# STM32_CAN-USB.net
KiCad netlist of a schematic drawn in EAGLE
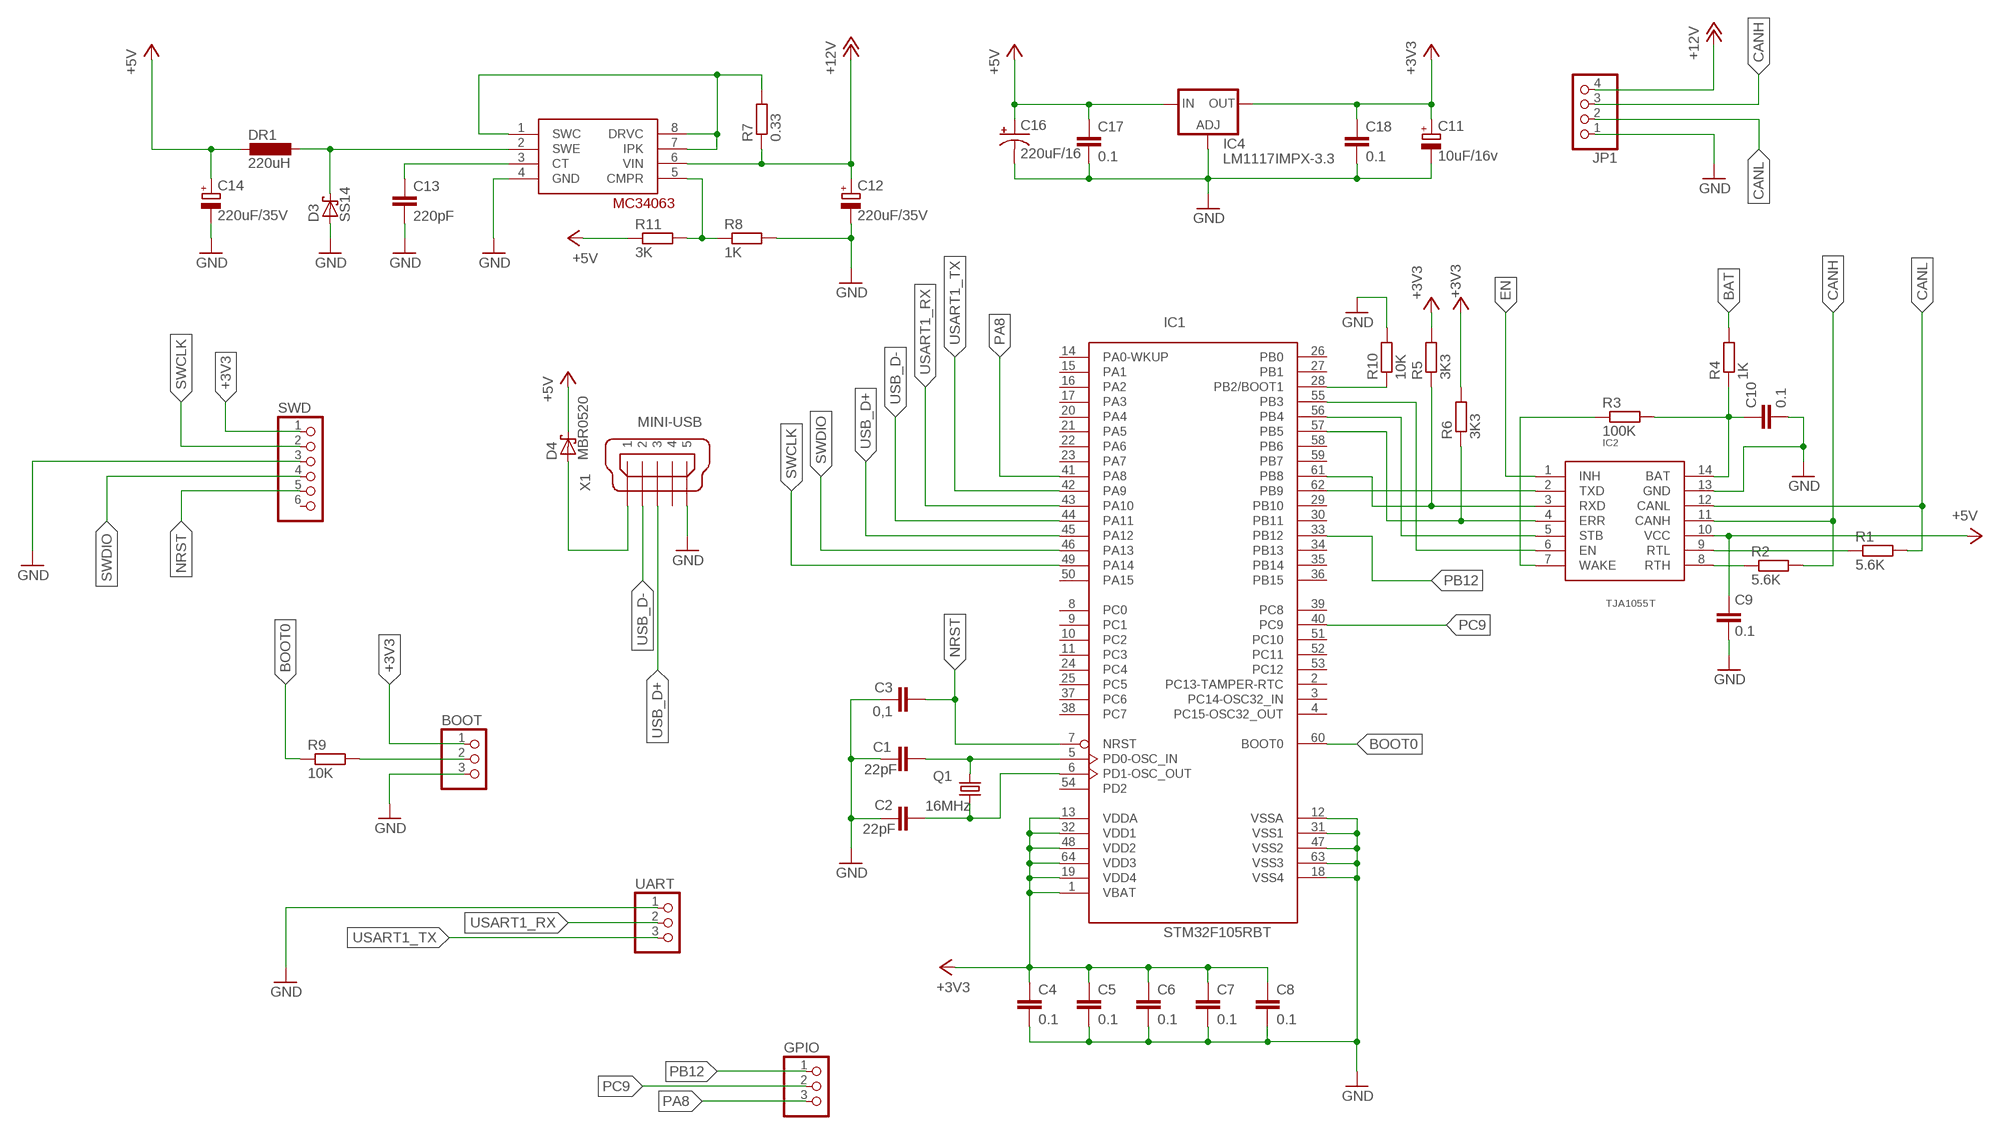
[diagram p0: schematic, sheet 1]

(export (version "E")
  (design (tool "Eeschema 10.0.6"))
  (components
    (comp (ref "BOOT")
      (value "PINHD-1X3")
      (footprint "eagle-import:1X03")
      (libsource (lib "eagle-import") (part "PINHD-1X3"))
    )
    (comp (ref "C1")
      (value "22pF")
      (footprint "eagle-import:C0805")
      (libsource (lib "eagle-import") (part "C-EUC0805"))
    )
    (comp (ref "C2")
      (value "22pF")
      (footprint "eagle-import:C0805")
      (libsource (lib "eagle-import") (part "C-EUC0805"))
    )
    (comp (ref "C3")
      (value "0,1")
      (footprint "eagle-import:C0805")
      (libsource (lib "eagle-import") (part "C-EUC0805"))
    )
    (comp (ref "C4")
      (value "0.1")
      (footprint "eagle-import:C0805")
      (libsource (lib "eagle-import") (part "C-EUC0805"))
    )
    (comp (ref "C5")
      (value "0.1")
      (footprint "eagle-import:C0805")
      (libsource (lib "eagle-import") (part "C-EUC0805"))
    )
    (comp (ref "C6")
      (value "0.1")
      (footprint "eagle-import:C0805")
      (libsource (lib "eagle-import") (part "C-EUC0805"))
    )
    (comp (ref "C7")
      (value "0.1")
      (footprint "eagle-import:C0805")
      (libsource (lib "eagle-import") (part "C-EUC0805"))
    )
    (comp (ref "C8")
      (value "0.1")
      (footprint "eagle-import:C0805")
      (libsource (lib "eagle-import") (part "C-EUC0805"))
    )
    (comp (ref "C9")
      (value "0.1")
      (footprint "eagle-import:C0805")
      (libsource (lib "eagle-import") (part "C-EUC0805"))
    )
    (comp (ref "C10")
      (value "0.1")
      (footprint "eagle-import:C0805")
      (libsource (lib "eagle-import") (part "C-EUC0805"))
    )
    (comp (ref "C11")
      (value "10uF/16v")
      (footprint "eagle-import:SMC_A")
      (libsource (lib "eagle-import") (part "CPOL-EUSMCA"))
    )
    (comp (ref "C12")
      (value "220uF/35V")
      (footprint "eagle-import:153CLV-0810")
      (libsource (lib "eagle-import") (part "CPOL-EU153CLV-0810"))
    )
    (comp (ref "C13")
      (value "220pF")
      (footprint "eagle-import:C0805")
      (libsource (lib "eagle-import") (part "C-EUC0805"))
    )
    (comp (ref "C14")
      (value "220uF/35V")
      (footprint "eagle-import:153CLV-0810")
      (libsource (lib "eagle-import") (part "CPOL-EU153CLV-0810"))
    )
    (comp (ref "C16")
      (value "220uF/16")
      (footprint "eagle-import:153CLV-0605")
      (libsource (lib "eagle-import") (part "CPOL-US153CLV-0605"))
    )
    (comp (ref "C17")
      (value "0.1")
      (footprint "eagle-import:C0805")
      (libsource (lib "eagle-import") (part "C-EUC0805"))
    )
    (comp (ref "C18")
      (value "0.1")
      (footprint "eagle-import:C0805")
      (libsource (lib "eagle-import") (part "C-EUC0805"))
    )
    (comp (ref "D3")
      (value "SS14")
      (footprint "eagle-import:SMA")
      (libsource (lib "eagle-import") (part "SS14"))
    )
    (comp (ref "D4")
      (value "MBR0520")
      (footprint "eagle-import:SOD123")
      (libsource (lib "eagle-import") (part "MBR0520"))
    )
    (comp (ref "DR1")
      (value "220uH")
      (footprint "eagle-import:MS85")
      (libsource (lib "eagle-import") (part "CDRH127"))
    )
    (comp (ref "GPIO")
      (value "PINHD-1X3")
      (footprint "eagle-import:1X03")
      (libsource (lib "eagle-import") (part "PINHD-1X3"))
    )
    (comp (ref "IC1")
      (value "STM32F105RBT")
      (footprint "eagle-import:LQFP64")
      (libsource (lib "eagle-import") (part "STM32F105RTB"))
    )
    (comp (ref "IC2")
      (value "TJA1055T")
      (footprint "eagle-import:SO-14W")
      (libsource (lib "eagle-import") (part "TJA1054T"))
    )
    (comp (ref "IC4")
      (value "LM1117IMPX-3.3")
      (footprint "eagle-import:SOT223")
      (libsource (lib "eagle-import") (part "LM1117IMPX-3.3"))
    )
    (comp (ref "JP1")
      (value "PINHD-1X4")
      (footprint "eagle-import:1X04")
      (libsource (lib "eagle-import") (part "PINHD-1X4"))
    )
    (comp (ref "MC34063")
      (value "MC34063")
      (footprint "eagle-import:SO8")
      (libsource (lib "eagle-import") (part "MC34063"))
    )
    (comp (ref "Q1")
      (value "16MHz")
      (footprint "eagle-import:HC49UP")
      (libsource (lib "eagle-import") (part "CRYSTALHC49UP"))
    )
    (comp (ref "R1")
      (value "5.6K")
      (footprint "eagle-import:R0805")
      (libsource (lib "eagle-import") (part "R-EU_R0805"))
    )
    (comp (ref "R2")
      (value "5.6K")
      (footprint "eagle-import:R0805")
      (libsource (lib "eagle-import") (part "R-EU_R0805"))
    )
    (comp (ref "R3")
      (value "100K")
      (footprint "eagle-import:R0805")
      (libsource (lib "eagle-import") (part "R-EU_R0805"))
    )
    (comp (ref "R4")
      (value "1K")
      (footprint "eagle-import:R0805")
      (libsource (lib "eagle-import") (part "R-EU_R0805"))
    )
    (comp (ref "R5")
      (value "3K3")
      (footprint "eagle-import:R0805")
      (libsource (lib "eagle-import") (part "R-EU_R0805"))
    )
    (comp (ref "R6")
      (value "3K3")
      (footprint "eagle-import:R0805")
      (libsource (lib "eagle-import") (part "R-EU_R0805"))
    )
    (comp (ref "R7")
      (value "0.33")
      (footprint "eagle-import:R0805")
      (libsource (lib "eagle-import") (part "R-EU_R0805"))
    )
    (comp (ref "R8")
      (value "1K")
      (footprint "eagle-import:R0805")
      (libsource (lib "eagle-import") (part "R-EU_R0805"))
    )
    (comp (ref "R9")
      (value "10K")
      (footprint "eagle-import:R0805")
      (libsource (lib "eagle-import") (part "R-EU_R0805"))
    )
    (comp (ref "R10")
      (value "10K")
      (footprint "eagle-import:R0805")
      (libsource (lib "eagle-import") (part "R-EU_R0805"))
    )
    (comp (ref "R11")
      (value "3K")
      (footprint "eagle-import:R0805")
      (libsource (lib "eagle-import") (part "R-EU_R0805"))
    )
    (comp (ref "SWD")
      (value "PINHD-1X6")
      (footprint "eagle-import:1X06")
      (libsource (lib "eagle-import") (part "PINHD-1X6"))
    )
    (comp (ref "UART")
      (value "PINHD-1X3")
      (footprint "eagle-import:1X03")
      (libsource (lib "eagle-import") (part "PINHD-1X3"))
    )
    (comp (ref "X1")
      (value "MINI-USB")
      (footprint "eagle-import:UX60-MB-5ST")
      (libsource (lib "eagle-import") (part "MINI-USB-UX60-MB-5ST"))
    )
  )
  (nets
    (net (code "1") (name "+3V3") (class "Default")
      (node (ref "BOOT") (pin "1") (pinfunction "1_1") (pintype "passive"))
      (node (ref "C11") (pin "+") (pinfunction "+_+") (pintype "passive"))
      (node (ref "C18") (pin "1") (pinfunction "1_1") (pintype "passive"))
      (node (ref "C4") (pin "1") (pinfunction "1_1") (pintype "passive"))
      (node (ref "C5") (pin "1") (pinfunction "1_1") (pintype "passive"))
      (node (ref "C6") (pin "1") (pinfunction "1_1") (pintype "passive"))
      (node (ref "C7") (pin "1") (pinfunction "1_1") (pintype "passive"))
      (node (ref "C8") (pin "1") (pinfunction "1_1") (pintype "passive"))
      (node (ref "IC1") (pin "1") (pinfunction "VBAT_1") (pintype "power_in"))
      (node (ref "IC1") (pin "13") (pinfunction "VDDA_13") (pintype "power_in"))
      (node (ref "IC1") (pin "19") (pinfunction "VDD4_19") (pintype "power_in"))
      (node (ref "IC1") (pin "32") (pinfunction "VDD1_32") (pintype "power_in"))
      (node (ref "IC1") (pin "48") (pinfunction "VDD2_48") (pintype "power_in"))
      (node (ref "IC1") (pin "64") (pinfunction "VDD3_64") (pintype "power_in"))
      (node (ref "IC4") (pin "2") (pinfunction "OUT_2") (pintype "passive"))
      (node (ref "IC4") (pin "4") (pinfunction "OUT_4") (pintype "passive"))
      (node (ref "R5") (pin "2") (pinfunction "2_2") (pintype "passive"))
      (node (ref "R6") (pin "2") (pinfunction "2_2") (pintype "passive"))
      (node (ref "SWD") (pin "1") (pinfunction "1_1") (pintype "passive"))
    )
    (net (code "2") (name "+5V") (class "Default")
      (node (ref "C14") (pin "+") (pinfunction "+_+") (pintype "passive"))
      (node (ref "C16") (pin "+") (pinfunction "+_+") (pintype "passive"))
      (node (ref "C17") (pin "1") (pinfunction "1_1") (pintype "passive"))
      (node (ref "C9") (pin "1") (pinfunction "1_1") (pintype "passive"))
      (node (ref "D4") (pin "C") (pinfunction "C_C") (pintype "passive"))
      (node (ref "DR1") (pin "P$1") (pinfunction "1_P$1") (pintype "passive"))
      (node (ref "IC2") (pin "10") (pinfunction "VCC_10") (pintype "power_in"))
      (node (ref "IC4") (pin "3") (pinfunction "IN_3") (pintype "input"))
      (node (ref "R11") (pin "1") (pinfunction "1_1") (pintype "passive"))
    )
    (net (code "3") (name "+12V") (class "Default")
      (node (ref "C12") (pin "+") (pinfunction "+_+") (pintype "passive"))
      (node (ref "JP1") (pin "4") (pinfunction "4_4") (pintype "passive"))
      (node (ref "MC34063") (pin "6") (pinfunction "VIN_6") (pintype "power_in"))
      (node (ref "R7") (pin "1") (pinfunction "1_1") (pintype "passive"))
    )
    (net (code "4") (name "BAT") (class "Default")
      (node (ref "R4") (pin "2") (pinfunction "2_2") (pintype "passive"))
    )
    (net (code "5") (name "BOOT0") (class "Default")
      (node (ref "IC1") (pin "60") (pinfunction "BOOT0_60") (pintype "input"))
      (node (ref "R9") (pin "1") (pinfunction "1_1") (pintype "passive"))
    )
    (net (code "6") (name "CANH") (class "Default")
      (node (ref "IC2") (pin "11") (pinfunction "CANH_11") (pintype "bidirectional"))
      (node (ref "JP1") (pin "3") (pinfunction "3_3") (pintype "passive"))
      (node (ref "R2") (pin "2") (pinfunction "2_2") (pintype "passive"))
    )
    (net (code "7") (name "CANL") (class "Default")
      (node (ref "IC2") (pin "12") (pinfunction "CANL_12") (pintype "bidirectional"))
      (node (ref "JP1") (pin "2") (pinfunction "2_2") (pintype "passive"))
      (node (ref "R1") (pin "2") (pinfunction "2_2") (pintype "passive"))
    )
    (net (code "8") (name "EN") (class "Default")
      (node (ref "IC2") (pin "1") (pinfunction "INH_1") (pintype "output"))
    )
    (net (code "9") (name "GND") (class "Default")
      (node (ref "BOOT") (pin "3") (pinfunction "3_3") (pintype "passive"))
      (node (ref "C1") (pin "2") (pinfunction "2_2") (pintype "passive"))
      (node (ref "C10") (pin "2") (pinfunction "2_2") (pintype "passive"))
      (node (ref "C11") (pin "-") (pinfunction "-_-") (pintype "passive"))
      (node (ref "C12") (pin "-") (pinfunction "-_-") (pintype "passive"))
      (node (ref "C13") (pin "2") (pinfunction "2_2") (pintype "passive"))
      (node (ref "C14") (pin "-") (pinfunction "-_-") (pintype "passive"))
      (node (ref "C16") (pin "-") (pinfunction "-_-") (pintype "passive"))
      (node (ref "C17") (pin "2") (pinfunction "2_2") (pintype "passive"))
      (node (ref "C18") (pin "2") (pinfunction "2_2") (pintype "passive"))
      (node (ref "C2") (pin "2") (pinfunction "2_2") (pintype "passive"))
      (node (ref "C3") (pin "1") (pinfunction "1_1") (pintype "passive"))
      (node (ref "C4") (pin "2") (pinfunction "2_2") (pintype "passive"))
      (node (ref "C5") (pin "2") (pinfunction "2_2") (pintype "passive"))
      (node (ref "C6") (pin "2") (pinfunction "2_2") (pintype "passive"))
      (node (ref "C7") (pin "2") (pinfunction "2_2") (pintype "passive"))
      (node (ref "C8") (pin "2") (pinfunction "2_2") (pintype "passive"))
      (node (ref "C9") (pin "2") (pinfunction "2_2") (pintype "passive"))
      (node (ref "D3") (pin "A") (pinfunction "A_A") (pintype "passive"))
      (node (ref "IC1") (pin "12") (pinfunction "VSSA_12") (pintype "power_in"))
      (node (ref "IC1") (pin "18") (pinfunction "VSS4_18") (pintype "power_in"))
      (node (ref "IC1") (pin "31") (pinfunction "VSS1_31") (pintype "power_in"))
      (node (ref "IC1") (pin "47") (pinfunction "VSS2_47") (pintype "power_in"))
      (node (ref "IC1") (pin "63") (pinfunction "VSS3_63") (pintype "power_in"))
      (node (ref "IC2") (pin "13") (pinfunction "GND_13") (pintype "power_in"))
      (node (ref "IC4") (pin "1") (pinfunction "ADJ_1") (pintype "input"))
      (node (ref "JP1") (pin "1") (pinfunction "1_1") (pintype "passive"))
      (node (ref "MC34063") (pin "4") (pinfunction "GND_4") (pintype "power_in"))
      (node (ref "R10") (pin "2") (pinfunction "2_2") (pintype "passive"))
      (node (ref "R8") (pin "2") (pinfunction "2_2") (pintype "passive"))
      (node (ref "SWD") (pin "3") (pinfunction "3_3") (pintype "passive"))
      (node (ref "UART") (pin "1") (pinfunction "1_1") (pintype "passive"))
      (node (ref "X1") (pin "5") (pinfunction "5_5") (pintype "input"))
      (node (ref "X1") (pin "M1") (pinfunction "5_M1") (pintype "input"))
      (node (ref "X1") (pin "M2") (pinfunction "5_M2") (pintype "input"))
    )
    (net (code "10") (name "NRST") (class "Default")
      (node (ref "C3") (pin "2") (pinfunction "2_2") (pintype "passive"))
      (node (ref "IC1") (pin "7") (pinfunction "NRST_7") (pintype "bidirectional"))
      (node (ref "SWD") (pin "5") (pinfunction "5_5") (pintype "passive"))
    )
    (net (code "11") (name "Net-(BOOT-Pad2)") (class "Default")
      (node (ref "BOOT") (pin "2") (pinfunction "2_2") (pintype "passive"))
      (node (ref "R9") (pin "2") (pinfunction "2_2") (pintype "passive"))
    )
    (net (code "12") (name "Net-(D4-PadA)") (class "Default")
      (node (ref "D4") (pin "A") (pinfunction "A_A") (pintype "passive"))
      (node (ref "X1") (pin "1") (pinfunction "1_1") (pintype "input"))
    )
    (net (code "13") (name "Net-(DR1-2)") (class "Default")
      (node (ref "D3") (pin "C") (pinfunction "C_C") (pintype "passive"))
      (node (ref "DR1") (pin "P$2") (pinfunction "2_P$2") (pintype "passive"))
      (node (ref "MC34063") (pin "2") (pinfunction "SWE_2") (pintype "output"))
    )
    (net (code "14") (name "Net-(IC1-PB2{slash}BOOT1)") (class "Default")
      (node (ref "IC1") (pin "28") (pinfunction "PB2/BOOT1_28") (pintype "bidirectional"))
      (node (ref "R10") (pin "1") (pinfunction "1_1") (pintype "passive"))
    )
    (net (code "15") (name "Net-(IC1-PB3)") (class "Default")
      (node (ref "IC1") (pin "55") (pinfunction "PB3_55") (pintype "bidirectional"))
      (node (ref "IC2") (pin "6") (pinfunction "EN_6") (pintype "input"))
    )
    (net (code "16") (name "Net-(IC1-PB4)") (class "Default")
      (node (ref "IC1") (pin "56") (pinfunction "PB4_56") (pintype "bidirectional"))
      (node (ref "IC2") (pin "5") (pinfunction "STB_5") (pintype "input"))
    )
    (net (code "17") (name "Net-(IC1-PB5)") (class "Default")
      (node (ref "IC1") (pin "57") (pinfunction "PB5_57") (pintype "bidirectional"))
      (node (ref "IC2") (pin "4") (pinfunction "ERR_4") (pintype "output"))
      (node (ref "R6") (pin "1") (pinfunction "1_1") (pintype "passive"))
    )
    (net (code "18") (name "Net-(IC1-PB8)") (class "Default")
      (node (ref "IC1") (pin "61") (pinfunction "PB8_61") (pintype "bidirectional"))
      (node (ref "IC2") (pin "3") (pinfunction "RXD_3") (pintype "bidirectional"))
      (node (ref "R5") (pin "1") (pinfunction "1_1") (pintype "passive"))
    )
    (net (code "19") (name "Net-(IC1-PB9)") (class "Default")
      (node (ref "IC1") (pin "62") (pinfunction "PB9_62") (pintype "bidirectional"))
      (node (ref "IC2") (pin "2") (pinfunction "TXD_2") (pintype "bidirectional"))
    )
    (net (code "20") (name "Net-(IC1-PD0-OSC_IN)") (class "Default")
      (node (ref "C1") (pin "1") (pinfunction "1_1") (pintype "passive"))
      (node (ref "IC1") (pin "5") (pinfunction "PD0-OSC_IN_5") (pintype "bidirectional"))
      (node (ref "Q1") (pin "2") (pinfunction "2_2") (pintype "passive"))
    )
    (net (code "21") (name "Net-(IC1-PD1-OSC_OUT)") (class "Default")
      (node (ref "C2") (pin "1") (pinfunction "1_1") (pintype "passive"))
      (node (ref "IC1") (pin "6") (pinfunction "PD1-OSC_OUT_6") (pintype "bidirectional"))
      (node (ref "Q1") (pin "1") (pinfunction "1_1") (pintype "passive"))
    )
    (net (code "22") (name "Net-(IC2-BAT)") (class "Default")
      (node (ref "C10") (pin "1") (pinfunction "1_1") (pintype "passive"))
      (node (ref "IC2") (pin "14") (pinfunction "BAT_14") (pintype "input"))
      (node (ref "R3") (pin "2") (pinfunction "2_2") (pintype "passive"))
      (node (ref "R4") (pin "1") (pinfunction "1_1") (pintype "passive"))
    )
    (net (code "23") (name "Net-(IC2-RTH)") (class "Default")
      (node (ref "IC2") (pin "8") (pinfunction "RTH_8") (pintype "bidirectional"))
      (node (ref "R2") (pin "1") (pinfunction "1_1") (pintype "passive"))
    )
    (net (code "24") (name "Net-(IC2-RTL)") (class "Default")
      (node (ref "IC2") (pin "9") (pinfunction "RTL_9") (pintype "bidirectional"))
      (node (ref "R1") (pin "1") (pinfunction "1_1") (pintype "passive"))
    )
    (net (code "25") (name "Net-(IC2-WAKE)") (class "Default")
      (node (ref "IC2") (pin "7") (pinfunction "WAKE_7") (pintype "input"))
      (node (ref "R3") (pin "1") (pinfunction "1_1") (pintype "passive"))
    )
    (net (code "26") (name "Net-(MC34063-CMPR)") (class "Default")
      (node (ref "MC34063") (pin "5") (pinfunction "CMPR_5") (pintype "input"))
      (node (ref "R11") (pin "2") (pinfunction "2_2") (pintype "passive"))
      (node (ref "R8") (pin "1") (pinfunction "1_1") (pintype "passive"))
    )
    (net (code "27") (name "Net-(MC34063-CT)") (class "Default")
      (node (ref "C13") (pin "1") (pinfunction "1_1") (pintype "passive"))
      (node (ref "MC34063") (pin "3") (pinfunction "CT_3") (pintype "input"))
    )
    (net (code "28") (name "Net-(MC34063-DRVC)") (class "Default")
      (node (ref "MC34063") (pin "1") (pinfunction "SWC_1") (pintype "input"))
      (node (ref "MC34063") (pin "7") (pinfunction "IPK_7") (pintype "input"))
      (node (ref "MC34063") (pin "8") (pinfunction "DRVC_8") (pintype "input"))
      (node (ref "R7") (pin "2") (pinfunction "2_2") (pintype "passive"))
    )
    (net (code "29") (name "PA8") (class "Default")
      (node (ref "GPIO") (pin "3") (pinfunction "3_3") (pintype "passive"))
      (node (ref "IC1") (pin "41") (pinfunction "PA8_41") (pintype "bidirectional"))
    )
    (net (code "30") (name "PB12") (class "Default")
      (node (ref "GPIO") (pin "1") (pinfunction "1_1") (pintype "passive"))
      (node (ref "IC1") (pin "33") (pinfunction "PB12_33") (pintype "bidirectional"))
    )
    (net (code "31") (name "PC9") (class "Default")
      (node (ref "GPIO") (pin "2") (pinfunction "2_2") (pintype "passive"))
      (node (ref "IC1") (pin "40") (pinfunction "PC9_40") (pintype "bidirectional"))
    )
    (net (code "32") (name "SWCLK") (class "Default")
      (node (ref "IC1") (pin "49") (pinfunction "PA14_49") (pintype "bidirectional"))
      (node (ref "SWD") (pin "2") (pinfunction "2_2") (pintype "passive"))
    )
    (net (code "33") (name "SWDIO") (class "Default")
      (node (ref "IC1") (pin "46") (pinfunction "PA13_46") (pintype "bidirectional"))
      (node (ref "SWD") (pin "4") (pinfunction "4_4") (pintype "passive"))
    )
    (net (code "34") (name "USART1_RX") (class "Default")
      (node (ref "IC1") (pin "43") (pinfunction "PA10_43") (pintype "bidirectional"))
      (node (ref "UART") (pin "2") (pinfunction "2_2") (pintype "passive"))
    )
    (net (code "35") (name "USART1_TX") (class "Default")
      (node (ref "IC1") (pin "42") (pinfunction "PA9_42") (pintype "bidirectional"))
      (node (ref "UART") (pin "3") (pinfunction "3_3") (pintype "passive"))
    )
    (net (code "36") (name "USB_D+") (class "Default")
      (node (ref "IC1") (pin "45") (pinfunction "PA12_45") (pintype "bidirectional"))
      (node (ref "X1") (pin "3") (pinfunction "3_3") (pintype "input"))
    )
    (net (code "37") (name "USB_D-") (class "Default")
      (node (ref "IC1") (pin "44") (pinfunction "PA11_44") (pintype "bidirectional"))
      (node (ref "X1") (pin "2") (pinfunction "2_2") (pintype "input"))
    )
    (net (code "38") (name "unconnected-(IC1-PA0-WKUP-Pad14)") (class "Default")
      (node (ref "IC1") (pin "14") (pinfunction "PA0-WKUP_14") (pintype "bidirectional"))
    )
    (net (code "39") (name "unconnected-(IC1-PA1-Pad15)") (class "Default")
      (node (ref "IC1") (pin "15") (pinfunction "PA1_15") (pintype "bidirectional"))
    )
    (net (code "40") (name "unconnected-(IC1-PA2-Pad16)") (class "Default")
      (node (ref "IC1") (pin "16") (pinfunction "PA2_16") (pintype "bidirectional"))
    )
    (net (code "41") (name "unconnected-(IC1-PA3-Pad17)") (class "Default")
      (node (ref "IC1") (pin "17") (pinfunction "PA3_17") (pintype "bidirectional"))
    )
    (net (code "42") (name "unconnected-(IC1-PA4-Pad20)") (class "Default")
      (node (ref "IC1") (pin "20") (pinfunction "PA4_20") (pintype "bidirectional"))
    )
    (net (code "43") (name "unconnected-(IC1-PA5-Pad21)") (class "Default")
      (node (ref "IC1") (pin "21") (pinfunction "PA5_21") (pintype "bidirectional"))
    )
    (net (code "44") (name "unconnected-(IC1-PA6-Pad22)") (class "Default")
      (node (ref "IC1") (pin "22") (pinfunction "PA6_22") (pintype "bidirectional"))
    )
    (net (code "45") (name "unconnected-(IC1-PA7-Pad23)") (class "Default")
      (node (ref "IC1") (pin "23") (pinfunction "PA7_23") (pintype "bidirectional"))
    )
    (net (code "46") (name "unconnected-(IC1-PA15-Pad50)") (class "Default")
      (node (ref "IC1") (pin "50") (pinfunction "PA15_50") (pintype "bidirectional"))
    )
    (net (code "47") (name "unconnected-(IC1-PB0-Pad26)") (class "Default")
      (node (ref "IC1") (pin "26") (pinfunction "PB0_26") (pintype "bidirectional"))
    )
    (net (code "48") (name "unconnected-(IC1-PB1-Pad27)") (class "Default")
      (node (ref "IC1") (pin "27") (pinfunction "PB1_27") (pintype "bidirectional"))
    )
    (net (code "49") (name "unconnected-(IC1-PB6-Pad58)") (class "Default")
      (node (ref "IC1") (pin "58") (pinfunction "PB6_58") (pintype "bidirectional"))
    )
    (net (code "50") (name "unconnected-(IC1-PB7-Pad59)") (class "Default")
      (node (ref "IC1") (pin "59") (pinfunction "PB7_59") (pintype "bidirectional"))
    )
    (net (code "51") (name "unconnected-(IC1-PB10-Pad29)") (class "Default")
      (node (ref "IC1") (pin "29") (pinfunction "PB10_29") (pintype "bidirectional"))
    )
    (net (code "52") (name "unconnected-(IC1-PB11-Pad30)") (class "Default")
      (node (ref "IC1") (pin "30") (pinfunction "PB11_30") (pintype "bidirectional"))
    )
    (net (code "53") (name "unconnected-(IC1-PB13-Pad34)") (class "Default")
      (node (ref "IC1") (pin "34") (pinfunction "PB13_34") (pintype "bidirectional"))
    )
    (net (code "54") (name "unconnected-(IC1-PB14-Pad35)") (class "Default")
      (node (ref "IC1") (pin "35") (pinfunction "PB14_35") (pintype "bidirectional"))
    )
    (net (code "55") (name "unconnected-(IC1-PB15-Pad36)") (class "Default")
      (node (ref "IC1") (pin "36") (pinfunction "PB15_36") (pintype "bidirectional"))
    )
    (net (code "56") (name "unconnected-(IC1-PC0-Pad8)") (class "Default")
      (node (ref "IC1") (pin "8") (pinfunction "PC0_8") (pintype "bidirectional"))
    )
    (net (code "57") (name "unconnected-(IC1-PC1-Pad9)") (class "Default")
      (node (ref "IC1") (pin "9") (pinfunction "PC1_9") (pintype "bidirectional"))
    )
    (net (code "58") (name "unconnected-(IC1-PC2-Pad10)") (class "Default")
      (node (ref "IC1") (pin "10") (pinfunction "PC2_10") (pintype "bidirectional"))
    )
    (net (code "59") (name "unconnected-(IC1-PC3-Pad11)") (class "Default")
      (node (ref "IC1") (pin "11") (pinfunction "PC3_11") (pintype "bidirectional"))
    )
    (net (code "60") (name "unconnected-(IC1-PC4-Pad24)") (class "Default")
      (node (ref "IC1") (pin "24") (pinfunction "PC4_24") (pintype "bidirectional"))
    )
    (net (code "61") (name "unconnected-(IC1-PC5-Pad25)") (class "Default")
      (node (ref "IC1") (pin "25") (pinfunction "PC5_25") (pintype "bidirectional"))
    )
    (net (code "62") (name "unconnected-(IC1-PC6-Pad37)") (class "Default")
      (node (ref "IC1") (pin "37") (pinfunction "PC6_37") (pintype "bidirectional"))
    )
    (net (code "63") (name "unconnected-(IC1-PC7-Pad38)") (class "Default")
      (node (ref "IC1") (pin "38") (pinfunction "PC7_38") (pintype "bidirectional"))
    )
    (net (code "64") (name "unconnected-(IC1-PC8-Pad39)") (class "Default")
      (node (ref "IC1") (pin "39") (pinfunction "PC8_39") (pintype "bidirectional"))
    )
    (net (code "65") (name "unconnected-(IC1-PC10-Pad51)") (class "Default")
      (node (ref "IC1") (pin "51") (pinfunction "PC10_51") (pintype "bidirectional"))
    )
    (net (code "66") (name "unconnected-(IC1-PC11-Pad52)") (class "Default")
      (node (ref "IC1") (pin "52") (pinfunction "PC11_52") (pintype "bidirectional"))
    )
    (net (code "67") (name "unconnected-(IC1-PC12-Pad53)") (class "Default")
      (node (ref "IC1") (pin "53") (pinfunction "PC12_53") (pintype "bidirectional"))
    )
    (net (code "68") (name "unconnected-(IC1-PC13-TAMPER-RTC-Pad2)") (class "Default")
      (node (ref "IC1") (pin "2") (pinfunction "PC13-TAMPER-RTC_2") (pintype "bidirectional"))
    )
    (net (code "69") (name "unconnected-(IC1-PC14-OSC32_IN-Pad3)") (class "Default")
      (node (ref "IC1") (pin "3") (pinfunction "PC14-OSC32_IN_3") (pintype "bidirectional"))
    )
    (net (code "70") (name "unconnected-(IC1-PC15-OSC32_OUT-Pad4)") (class "Default")
      (node (ref "IC1") (pin "4") (pinfunction "PC15-OSC32_OUT_4") (pintype "bidirectional"))
    )
    (net (code "71") (name "unconnected-(IC1-PD2-Pad54)") (class "Default")
      (node (ref "IC1") (pin "54") (pinfunction "PD2_54") (pintype "bidirectional"))
    )
    (net (code "72") (name "unconnected-(SWD-Pad6)") (class "Default")
      (node (ref "SWD") (pin "6") (pinfunction "6_6") (pintype "passive"))
    )
    (net (code "73") (name "unconnected-(X1-Pad4)") (class "Default")
      (node (ref "X1") (pin "4") (pinfunction "4_4") (pintype "input"))
    )
  )
)
